# mLRS-tx-dualE22-top-v042.net
KiCad netlist of a schematic drawn in EAGLE
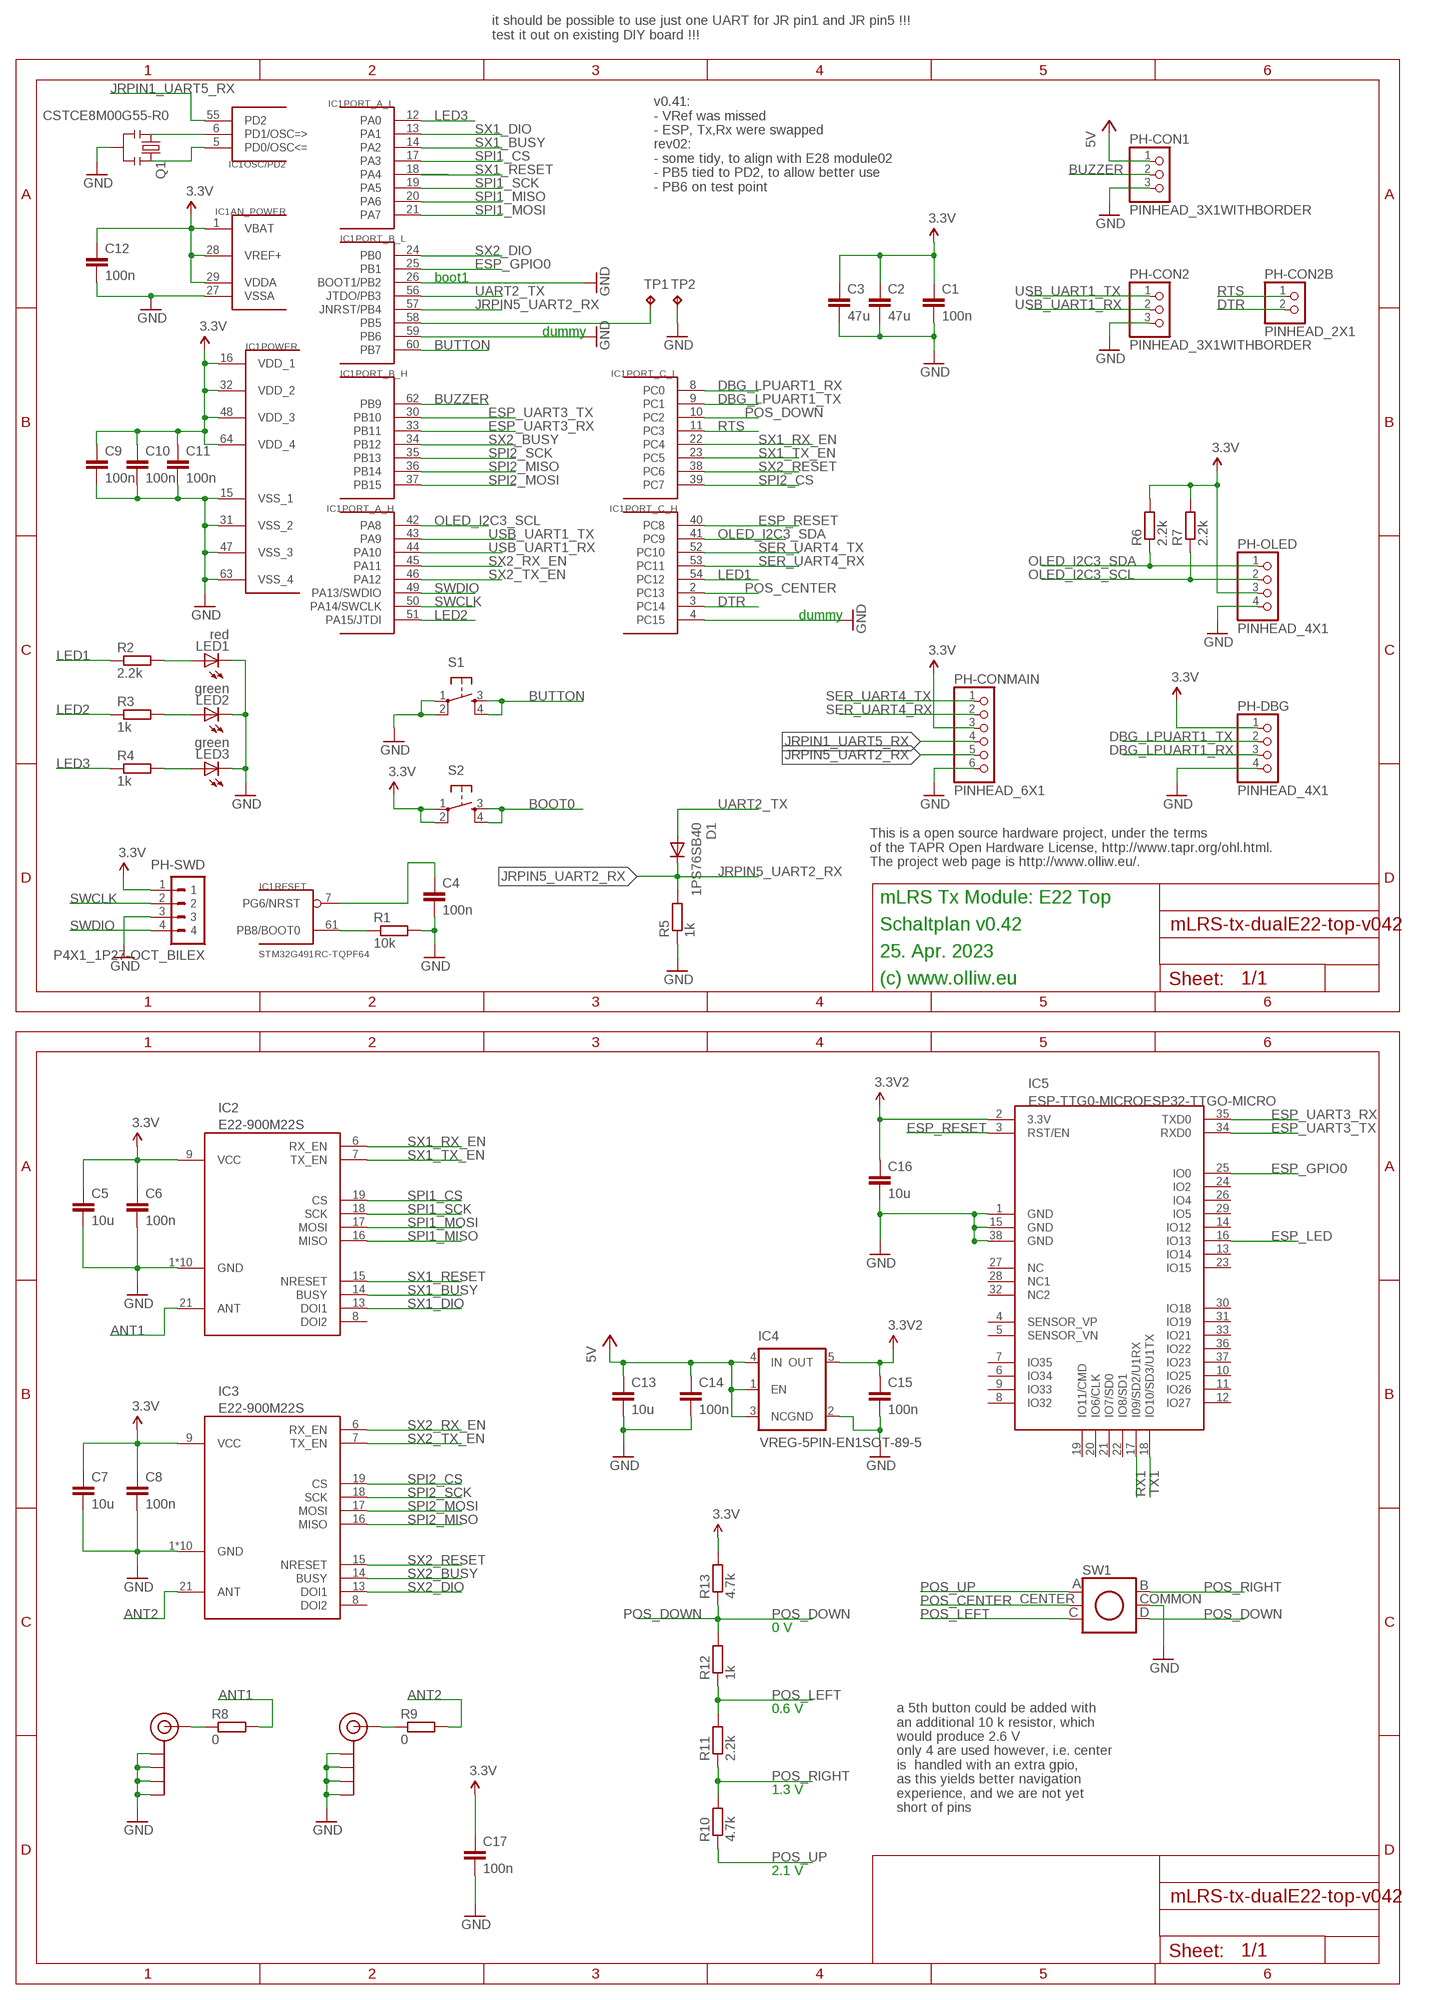
[diagram p0: schematic, sheet 1]

(export (version "E")
  (design (tool "Eeschema 10.0.6"))
  (components
    (comp (ref "C1")
      (value "100n")
      (footprint "eagle-import:C0402")
      (libsource (lib "eagle-import") (part "C-EUC0402"))
    )
    (comp (ref "C2")
      (value "47u")
      (footprint "eagle-import:C1210")
      (libsource (lib "eagle-import") (part "C-EUC1210"))
    )
    (comp (ref "C3")
      (value "47u")
      (footprint "eagle-import:C1206K")
      (libsource (lib "eagle-import") (part "C-EUC1206K"))
    )
    (comp (ref "C4")
      (value "100n")
      (footprint "eagle-import:C0402")
      (libsource (lib "eagle-import") (part "C-EUC0402"))
    )
    (comp (ref "C5")
      (value "10u")
      (footprint "eagle-import:C0603")
      (libsource (lib "eagle-import") (part "C-EUC0603"))
    )
    (comp (ref "C6")
      (value "100n")
      (footprint "eagle-import:C0402")
      (libsource (lib "eagle-import") (part "C-EUC0402"))
    )
    (comp (ref "C7")
      (value "10u")
      (footprint "eagle-import:C0603")
      (libsource (lib "eagle-import") (part "C-EUC0603"))
    )
    (comp (ref "C8")
      (value "100n")
      (footprint "eagle-import:C0402")
      (libsource (lib "eagle-import") (part "C-EUC0402"))
    )
    (comp (ref "C9")
      (value "100n")
      (footprint "eagle-import:C0402")
      (libsource (lib "eagle-import") (part "C-EUC0402"))
    )
    (comp (ref "C10")
      (value "100n")
      (footprint "eagle-import:C0402")
      (libsource (lib "eagle-import") (part "C-EUC0402"))
    )
    (comp (ref "C11")
      (value "100n")
      (footprint "eagle-import:C0402")
      (libsource (lib "eagle-import") (part "C-EUC0402"))
    )
    (comp (ref "C12")
      (value "100n")
      (footprint "eagle-import:C0402")
      (libsource (lib "eagle-import") (part "C-EUC0402"))
    )
    (comp (ref "C13")
      (value "10u")
      (footprint "eagle-import:C0603")
      (libsource (lib "eagle-import") (part "C-EUC0603"))
    )
    (comp (ref "C14")
      (value "100n")
      (footprint "eagle-import:C0402")
      (libsource (lib "eagle-import") (part "C-EUC0402"))
    )
    (comp (ref "C15")
      (value "100n")
      (footprint "eagle-import:C0402")
      (libsource (lib "eagle-import") (part "C-EUC0402"))
    )
    (comp (ref "C16")
      (value "10u")
      (footprint "eagle-import:C0603")
      (libsource (lib "eagle-import") (part "C-EUC0603"))
    )
    (comp (ref "C17")
      (value "100n")
      (footprint "eagle-import:C0402")
      (libsource (lib "eagle-import") (part "C-EUC0402"))
    )
    (comp (ref "D1")
      (value "1PS76SB40")
      (footprint "eagle-import:SOD110-R")
      (libsource (lib "eagle-import") (part "DIODE-SOD110-R"))
    )
    (comp (ref "IC1")
      (value "STM32G491RC-TQPF64")
      (footprint "eagle-import:TQFP64")
      (libsource (lib "eagle-import") (part "STM32G4X1RX-TQPF64"))
    )
    (comp (ref "IC2")
      (value "E22-900M22S")
      (footprint "eagle-import:E22-900M22S")
      (libsource (lib "eagle-import") (part "E22-900M22S"))
    )
    (comp (ref "IC3")
      (value "E22-900M22S")
      (footprint "eagle-import:E22-900M22S")
      (libsource (lib "eagle-import") (part "E22-900M22S"))
    )
    (comp (ref "IC4")
      (value "VREG-5PIN-EN1SOT-89-5")
      (footprint "eagle-import:SOT-89-5")
      (libsource (lib "eagle-import") (part "VREG-5PIN-EN1SOT-89-5"))
    )
    (comp (ref "IC5")
      (value "ESP-TTG0-MICROESP32-TTGO-MICRO")
      (footprint "eagle-import:ESP32-TTGO-MICRO")
      (libsource (lib "eagle-import") (part "ESP-TTG0-MICROESP32-TTGO-MICRO"))
    )
    (comp (ref "LED1")
      (value "red")
      (footprint "eagle-import:CHIPLED_0603")
      (libsource (lib "eagle-import") (part "LEDCHIPLED_0603"))
    )
    (comp (ref "LED2")
      (value "green")
      (footprint "eagle-import:CHIPLED_0603")
      (libsource (lib "eagle-import") (part "LEDCHIPLED_0603"))
    )
    (comp (ref "LED3")
      (value "green")
      (footprint "eagle-import:CHIPLED_0603")
      (libsource (lib "eagle-import") (part "LEDCHIPLED_0603"))
    )
    (comp (ref "PH-CON1")
      (value "PINHEAD_3X1WITHBORDER")
      (footprint "eagle-import:PINHEAD_3X1")
      (libsource (lib "eagle-import") (part "PINHEAD_3X1WITHBORDER"))
    )
    (comp (ref "PH-CON2")
      (value "PINHEAD_3X1WITHBORDER")
      (footprint "eagle-import:PINHEAD_3X1")
      (libsource (lib "eagle-import") (part "PINHEAD_3X1WITHBORDER"))
    )
    (comp (ref "PH-CON2B")
      (value "PINHEAD_2X1")
      (footprint "eagle-import:PINHEAD_2X1")
      (libsource (lib "eagle-import") (part "PINHEAD_2X1"))
    )
    (comp (ref "PH-CONMAIN")
      (value "PINHEAD_6X1")
      (footprint "eagle-import:PINHEAD_6X1")
      (libsource (lib "eagle-import") (part "PINHEAD_6X1"))
    )
    (comp (ref "PH-DBG")
      (value "PINHEAD_4X1")
      (footprint "eagle-import:PINHEAD_4X1")
      (libsource (lib "eagle-import") (part "PINHEAD_4X1"))
    )
    (comp (ref "PH-OLED")
      (value "PINHEAD_4X1")
      (footprint "eagle-import:PINHEAD_4X1")
      (libsource (lib "eagle-import") (part "PINHEAD_4X1"))
    )
    (comp (ref "PH-SWD")
      (value "P4X1_1P27-OCT_BILEX")
      (footprint "eagle-import:4X1_1P27_OCT_BILEX")
      (libsource (lib "eagle-import") (part "P4X1_1P27-OCT_BILEX"))
    )
    (comp (ref "Q1")
      (value "CSTCE8M00G55-R0")
      (footprint "eagle-import:RESONATOR-SMD")
      (libsource (lib "eagle-import") (part "RESONATORSMD"))
    )
    (comp (ref "R1")
      (value "10k")
      (footprint "eagle-import:R0402")
      (libsource (lib "eagle-import") (part "R-EU_R0402"))
    )
    (comp (ref "R2")
      (value "2.2k")
      (footprint "eagle-import:R0402")
      (libsource (lib "eagle-import") (part "R-EU_R0402"))
    )
    (comp (ref "R3")
      (value "1k")
      (footprint "eagle-import:R0402")
      (libsource (lib "eagle-import") (part "R-EU_R0402"))
    )
    (comp (ref "R4")
      (value "1k")
      (footprint "eagle-import:R0402")
      (libsource (lib "eagle-import") (part "R-EU_R0402"))
    )
    (comp (ref "R5")
      (value "1k")
      (footprint "eagle-import:R0402")
      (libsource (lib "eagle-import") (part "R-EU_R0402"))
    )
    (comp (ref "R6")
      (value "2.2k")
      (footprint "eagle-import:R0402")
      (libsource (lib "eagle-import") (part "R-EU_R0402"))
    )
    (comp (ref "R7")
      (value "2.2k")
      (footprint "eagle-import:R0402")
      (libsource (lib "eagle-import") (part "R-EU_R0402"))
    )
    (comp (ref "R8")
      (value "0")
      (footprint "eagle-import:R0402")
      (libsource (lib "eagle-import") (part "R-EU_R0402"))
    )
    (comp (ref "R9")
      (value "0")
      (footprint "eagle-import:R0402")
      (libsource (lib "eagle-import") (part "R-EU_R0402"))
    )
    (comp (ref "R10")
      (value "4.7k")
      (footprint "eagle-import:R0402")
      (libsource (lib "eagle-import") (part "R-EU_R0402"))
    )
    (comp (ref "R11")
      (value "2.2k")
      (footprint "eagle-import:R0402")
      (libsource (lib "eagle-import") (part "R-EU_R0402"))
    )
    (comp (ref "R12")
      (value "1k")
      (footprint "eagle-import:R0402")
      (libsource (lib "eagle-import") (part "R-EU_R0402"))
    )
    (comp (ref "R13")
      (value "4.7k")
      (footprint "eagle-import:R0402")
      (libsource (lib "eagle-import") (part "R-EU_R0402"))
    )
    (comp (ref "RF1")
      (value "SMA_EDGE")
      (footprint "eagle-import:SMA-EDGE")
      (libsource (lib "eagle-import") (part "SMA_EDGE"))
    )
    (comp (ref "RF2")
      (value "SMA_EDGE")
      (footprint "eagle-import:SMA-EDGE")
      (libsource (lib "eagle-import") (part "SMA_EDGE"))
    )
    (comp (ref "S1")
      (value "TAC_SWITCHPTH")
      (footprint "eagle-import:TACTILE-PTH")
      (libsource (lib "eagle-import") (part "TAC_SWITCHPTH"))
    )
    (comp (ref "S2")
      (value "TAC_SWITCHPTH")
      (footprint "eagle-import:TACTILE-PTH")
      (libsource (lib "eagle-import") (part "TAC_SWITCHPTH"))
    )
    (comp (ref "SW1")
      (value "JOYSTICK-5WAY")
      (footprint "eagle-import:JOYSTICK-5WAY")
      (libsource (lib "eagle-import") (part "JOYSTICK-5WAY"))
    )
    (comp (ref "TP1")
      (value "TPB1,27")
      (footprint "eagle-import:B1,27")
      (libsource (lib "eagle-import") (part "TPB1,27"))
    )
    (comp (ref "TP2")
      (value "TPB1,27")
      (footprint "eagle-import:B1,27")
      (libsource (lib "eagle-import") (part "TPB1,27"))
    )
  )
  (nets
    (net (code "1") (name "/ANT1") (class "Default")
      (node (ref "IC2") (pin "21") (pinfunction "ANT_21") (pintype "bidirectional"))
      (node (ref "R8") (pin "2") (pinfunction "2_2") (pintype "passive"))
    )
    (net (code "2") (name "/ANT2") (class "Default")
      (node (ref "IC3") (pin "21") (pinfunction "ANT_21") (pintype "bidirectional"))
      (node (ref "R9") (pin "2") (pinfunction "2_2") (pintype "passive"))
    )
    (net (code "3") (name "/BOOT0") (class "Default")
      (node (ref "IC1") (pin "61") (pinfunction "PB8/BOOT0_61") (pintype "input"))
      (node (ref "R1") (pin "1") (pinfunction "1_1") (pintype "passive"))
      (node (ref "S2") (pin "3") (pinfunction "3_3") (pintype "passive"))
      (node (ref "S2") (pin "4") (pinfunction "4_4") (pintype "passive"))
    )
    (net (code "4") (name "/BUTTON") (class "Default")
      (node (ref "IC1") (pin "60") (pinfunction "PB7_60") (pintype "bidirectional"))
      (node (ref "S1") (pin "3") (pinfunction "3_3") (pintype "passive"))
      (node (ref "S1") (pin "4") (pinfunction "4_4") (pintype "passive"))
    )
    (net (code "5") (name "/BUZZER") (class "Default")
      (node (ref "IC1") (pin "62") (pinfunction "PB9_62") (pintype "bidirectional"))
      (node (ref "PH-CON1") (pin "2") (pinfunction "3_2") (pintype "passive"))
    )
    (net (code "6") (name "/DBG_LPUART1_RX") (class "Default")
      (node (ref "IC1") (pin "8") (pinfunction "PC0_8") (pintype "bidirectional"))
      (node (ref "PH-DBG") (pin "3") (pinfunction "3_3") (pintype "passive"))
    )
    (net (code "7") (name "/DBG_LPUART1_TX") (class "Default")
      (node (ref "IC1") (pin "9") (pinfunction "PC1_9") (pintype "bidirectional"))
      (node (ref "PH-DBG") (pin "2") (pinfunction "2_2") (pintype "passive"))
    )
    (net (code "8") (name "/DTR") (class "Default")
      (node (ref "IC1") (pin "3") (pinfunction "PC14_3") (pintype "bidirectional"))
      (node (ref "PH-CON2B") (pin "2") (pinfunction "2_2") (pintype "passive"))
    )
    (net (code "9") (name "/ESP_GPIO0") (class "Default")
      (node (ref "IC1") (pin "25") (pinfunction "PB1_25") (pintype "bidirectional"))
      (node (ref "IC5") (pin "25") (pinfunction "IO0_25") (pintype "bidirectional"))
    )
    (net (code "10") (name "/ESP_LED") (class "Default")
      (node (ref "IC5") (pin "16") (pinfunction "IO13_16") (pintype "bidirectional"))
    )
    (net (code "11") (name "/ESP_RESET") (class "Default")
      (node (ref "IC1") (pin "40") (pinfunction "PC8_40") (pintype "bidirectional"))
      (node (ref "IC5") (pin "3") (pinfunction "RST/EN_3") (pintype "input"))
    )
    (net (code "12") (name "/ESP_UART3_RX") (class "Default")
      (node (ref "IC1") (pin "33") (pinfunction "PB11_33") (pintype "bidirectional"))
      (node (ref "IC5") (pin "35") (pinfunction "TXD0_35") (pintype "bidirectional"))
    )
    (net (code "13") (name "/ESP_UART3_TX") (class "Default")
      (node (ref "IC1") (pin "30") (pinfunction "PB10_30") (pintype "bidirectional"))
      (node (ref "IC5") (pin "34") (pinfunction "RXD0_34") (pintype "bidirectional"))
    )
    (net (code "14") (name "/LED1") (class "Default")
      (node (ref "IC1") (pin "54") (pinfunction "PC12_54") (pintype "bidirectional"))
      (node (ref "R2") (pin "1") (pinfunction "1_1") (pintype "passive"))
    )
    (net (code "15") (name "/LED2") (class "Default")
      (node (ref "IC1") (pin "51") (pinfunction "PA15/JTDI_51") (pintype "bidirectional"))
      (node (ref "R3") (pin "1") (pinfunction "1_1") (pintype "passive"))
    )
    (net (code "16") (name "/LED3") (class "Default")
      (node (ref "IC1") (pin "12") (pinfunction "PA0_12") (pintype "bidirectional"))
      (node (ref "R4") (pin "1") (pinfunction "1_1") (pintype "passive"))
    )
    (net (code "17") (name "/OLED_I2C3_SCL") (class "Default")
      (node (ref "IC1") (pin "42") (pinfunction "PA8_42") (pintype "bidirectional"))
      (node (ref "PH-OLED") (pin "2") (pinfunction "2_2") (pintype "passive"))
      (node (ref "R7") (pin "1") (pinfunction "1_1") (pintype "passive"))
    )
    (net (code "18") (name "/OLED_I2C3_SDA") (class "Default")
      (node (ref "IC1") (pin "41") (pinfunction "PC9_41") (pintype "bidirectional"))
      (node (ref "PH-OLED") (pin "1") (pinfunction "1_1") (pintype "passive"))
      (node (ref "R6") (pin "1") (pinfunction "1_1") (pintype "passive"))
    )
    (net (code "19") (name "/POS_CENTER") (class "Default")
      (node (ref "IC1") (pin "2") (pinfunction "PC13_2") (pintype "bidirectional"))
      (node (ref "SW1") (pin "2") (pinfunction "CENTER_2") (pintype "bidirectional"))
    )
    (net (code "20") (name "/POS_DOWN") (class "Default")
      (node (ref "IC1") (pin "10") (pinfunction "PC2_10") (pintype "bidirectional"))
      (node (ref "R12") (pin "2") (pinfunction "2_2") (pintype "passive"))
      (node (ref "R13") (pin "1") (pinfunction "1_1") (pintype "passive"))
      (node (ref "SW1") (pin "6") (pinfunction "D_6") (pintype "bidirectional"))
    )
    (net (code "21") (name "/POS_LEFT") (class "Default")
      (node (ref "R11") (pin "2") (pinfunction "2_2") (pintype "passive"))
      (node (ref "R12") (pin "1") (pinfunction "1_1") (pintype "passive"))
      (node (ref "SW1") (pin "3") (pinfunction "C_3") (pintype "bidirectional"))
    )
    (net (code "22") (name "/POS_RIGHT") (class "Default")
      (node (ref "R10") (pin "2") (pinfunction "2_2") (pintype "passive"))
      (node (ref "R11") (pin "1") (pinfunction "1_1") (pintype "passive"))
      (node (ref "SW1") (pin "4") (pinfunction "B_4") (pintype "bidirectional"))
    )
    (net (code "23") (name "/POS_UP") (class "Default")
      (node (ref "R10") (pin "1") (pinfunction "1_1") (pintype "passive"))
      (node (ref "SW1") (pin "1") (pinfunction "A_1") (pintype "bidirectional"))
    )
    (net (code "24") (name "/RTS") (class "Default")
      (node (ref "IC1") (pin "11") (pinfunction "PC3_11") (pintype "bidirectional"))
      (node (ref "PH-CON2B") (pin "1") (pinfunction "1_1") (pintype "passive"))
    )
    (net (code "25") (name "/RX1") (class "Default")
      (node (ref "IC5") (pin "17") (pinfunction "I09/SD2/U1RX_17") (pintype "bidirectional"))
    )
    (net (code "26") (name "/SER_UART4_RX") (class "Default")
      (node (ref "IC1") (pin "53") (pinfunction "PC11_53") (pintype "bidirectional"))
      (node (ref "PH-CONMAIN") (pin "2") (pinfunction "2_2") (pintype "passive"))
    )
    (net (code "27") (name "/SER_UART4_TX") (class "Default")
      (node (ref "IC1") (pin "52") (pinfunction "PC10_52") (pintype "bidirectional"))
      (node (ref "PH-CONMAIN") (pin "1") (pinfunction "1_1") (pintype "passive"))
    )
    (net (code "28") (name "/SPI1_CS") (class "Default")
      (node (ref "IC1") (pin "17") (pinfunction "PA3_17") (pintype "bidirectional"))
      (node (ref "IC2") (pin "19") (pinfunction "CS_19") (pintype "bidirectional"))
    )
    (net (code "29") (name "/SPI1_MISO") (class "Default")
      (node (ref "IC1") (pin "20") (pinfunction "PA6_20") (pintype "bidirectional"))
      (node (ref "IC2") (pin "16") (pinfunction "MISO_16") (pintype "bidirectional"))
    )
    (net (code "30") (name "/SPI1_MOSI") (class "Default")
      (node (ref "IC1") (pin "21") (pinfunction "PA7_21") (pintype "bidirectional"))
      (node (ref "IC2") (pin "17") (pinfunction "MOSI_17") (pintype "bidirectional"))
    )
    (net (code "31") (name "/SPI1_SCK") (class "Default")
      (node (ref "IC1") (pin "19") (pinfunction "PA5_19") (pintype "bidirectional"))
      (node (ref "IC2") (pin "18") (pinfunction "SCK_18") (pintype "bidirectional"))
    )
    (net (code "32") (name "/SPI2_CS") (class "Default")
      (node (ref "IC1") (pin "39") (pinfunction "PC7_39") (pintype "bidirectional"))
      (node (ref "IC3") (pin "19") (pinfunction "CS_19") (pintype "bidirectional"))
    )
    (net (code "33") (name "/SPI2_MISO") (class "Default")
      (node (ref "IC1") (pin "36") (pinfunction "PB14_36") (pintype "bidirectional"))
      (node (ref "IC3") (pin "16") (pinfunction "MISO_16") (pintype "bidirectional"))
    )
    (net (code "34") (name "/SPI2_MOSI") (class "Default")
      (node (ref "IC1") (pin "37") (pinfunction "PB15_37") (pintype "bidirectional"))
      (node (ref "IC3") (pin "17") (pinfunction "MOSI_17") (pintype "bidirectional"))
    )
    (net (code "35") (name "/SPI2_SCK") (class "Default")
      (node (ref "IC1") (pin "35") (pinfunction "PB13_35") (pintype "bidirectional"))
      (node (ref "IC3") (pin "18") (pinfunction "SCK_18") (pintype "bidirectional"))
    )
    (net (code "36") (name "/SWCLK") (class "Default")
      (node (ref "IC1") (pin "50") (pinfunction "PA14/SWCLK_50") (pintype "bidirectional"))
      (node (ref "PH-SWD") (pin "2") (pinfunction "2_2") (pintype "passive"))
    )
    (net (code "37") (name "/SWDIO") (class "Default")
      (node (ref "IC1") (pin "49") (pinfunction "PA13/SWDIO_49") (pintype "bidirectional"))
      (node (ref "PH-SWD") (pin "4") (pinfunction "4_4") (pintype "passive"))
    )
    (net (code "38") (name "/SX1_BUSY") (class "Default")
      (node (ref "IC1") (pin "14") (pinfunction "PA2_14") (pintype "bidirectional"))
      (node (ref "IC2") (pin "14") (pinfunction "BUSY_14") (pintype "bidirectional"))
    )
    (net (code "39") (name "/SX1_DIO") (class "Default")
      (node (ref "IC1") (pin "13") (pinfunction "PA1_13") (pintype "bidirectional"))
      (node (ref "IC2") (pin "13") (pinfunction "DOI1_13") (pintype "bidirectional"))
    )
    (net (code "40") (name "/SX1_RESET") (class "Default")
      (node (ref "IC1") (pin "18") (pinfunction "PA4_18") (pintype "bidirectional"))
      (node (ref "IC2") (pin "15") (pinfunction "NRESET_15") (pintype "input"))
    )
    (net (code "41") (name "/SX1_RX_EN") (class "Default")
      (node (ref "IC1") (pin "22") (pinfunction "PC4_22") (pintype "bidirectional"))
      (node (ref "IC2") (pin "6") (pinfunction "RX_EN_6") (pintype "bidirectional"))
    )
    (net (code "42") (name "/SX1_TX_EN") (class "Default")
      (node (ref "IC1") (pin "23") (pinfunction "PC5_23") (pintype "bidirectional"))
      (node (ref "IC2") (pin "7") (pinfunction "TX_EN_7") (pintype "bidirectional"))
    )
    (net (code "43") (name "/SX2_BUSY") (class "Default")
      (node (ref "IC1") (pin "34") (pinfunction "PB12_34") (pintype "bidirectional"))
      (node (ref "IC3") (pin "14") (pinfunction "BUSY_14") (pintype "bidirectional"))
    )
    (net (code "44") (name "/SX2_DIO") (class "Default")
      (node (ref "IC1") (pin "24") (pinfunction "PB0_24") (pintype "bidirectional"))
      (node (ref "IC3") (pin "13") (pinfunction "DOI1_13") (pintype "bidirectional"))
    )
    (net (code "45") (name "/SX2_RESET") (class "Default")
      (node (ref "IC1") (pin "38") (pinfunction "PC6_38") (pintype "bidirectional"))
      (node (ref "IC3") (pin "15") (pinfunction "NRESET_15") (pintype "input"))
    )
    (net (code "46") (name "/SX2_RX_EN") (class "Default")
      (node (ref "IC1") (pin "45") (pinfunction "PA11_45") (pintype "bidirectional"))
      (node (ref "IC3") (pin "6") (pinfunction "RX_EN_6") (pintype "bidirectional"))
    )
    (net (code "47") (name "/SX2_TX_EN") (class "Default")
      (node (ref "IC1") (pin "46") (pinfunction "PA12_46") (pintype "bidirectional"))
      (node (ref "IC3") (pin "7") (pinfunction "TX_EN_7") (pintype "bidirectional"))
    )
    (net (code "48") (name "/TX1") (class "Default")
      (node (ref "IC5") (pin "18") (pinfunction "IO10/SD3/U1TX_18") (pintype "bidirectional"))
    )
    (net (code "49") (name "/UART2_TX") (class "Default")
      (node (ref "D1") (pin "A") (pinfunction "A_A") (pintype "passive"))
      (node (ref "IC1") (pin "56") (pinfunction "JTDO/PB3_56") (pintype "bidirectional"))
    )
    (net (code "50") (name "/USB_UART1_RX") (class "Default")
      (node (ref "IC1") (pin "44") (pinfunction "PA10_44") (pintype "bidirectional"))
      (node (ref "PH-CON2") (pin "2") (pinfunction "3_2") (pintype "passive"))
    )
    (net (code "51") (name "/USB_UART1_TX") (class "Default")
      (node (ref "IC1") (pin "43") (pinfunction "PA9_43") (pintype "bidirectional"))
      (node (ref "PH-CON2") (pin "1") (pinfunction "1_1") (pintype "passive"))
    )
    (net (code "52") (name "3.3V") (class "Default")
      (node (ref "C1") (pin "1") (pinfunction "1_1") (pintype "passive"))
      (node (ref "C10") (pin "1") (pinfunction "1_1") (pintype "passive"))
      (node (ref "C11") (pin "1") (pinfunction "1_1") (pintype "passive"))
      (node (ref "C12") (pin "1") (pinfunction "1_1") (pintype "passive"))
      (node (ref "C17") (pin "1") (pinfunction "1_1") (pintype "passive"))
      (node (ref "C2") (pin "1") (pinfunction "1_1") (pintype "passive"))
      (node (ref "C3") (pin "1") (pinfunction "1_1") (pintype "passive"))
      (node (ref "C5") (pin "1") (pinfunction "1_1") (pintype "passive"))
      (node (ref "C6") (pin "1") (pinfunction "1_1") (pintype "passive"))
      (node (ref "C7") (pin "1") (pinfunction "1_1") (pintype "passive"))
      (node (ref "C8") (pin "1") (pinfunction "1_1") (pintype "passive"))
      (node (ref "C9") (pin "1") (pinfunction "1_1") (pintype "passive"))
      (node (ref "IC1") (pin "1") (pinfunction "VBAT_1") (pintype "power_in"))
      (node (ref "IC1") (pin "16") (pinfunction "VDD_1_16") (pintype "power_in"))
      (node (ref "IC1") (pin "28") (pinfunction "VREF+_28") (pintype "input"))
      (node (ref "IC1") (pin "29") (pinfunction "VDDA_29") (pintype "power_in"))
      (node (ref "IC1") (pin "32") (pinfunction "VDD_2_32") (pintype "power_in"))
      (node (ref "IC1") (pin "48") (pinfunction "VDD_3_48") (pintype "power_in"))
      (node (ref "IC1") (pin "64") (pinfunction "VDD_4_64") (pintype "power_in"))
      (node (ref "IC2") (pin "9") (pinfunction "VCC_9") (pintype "power_in"))
      (node (ref "IC3") (pin "9") (pinfunction "VCC_9") (pintype "power_in"))
      (node (ref "PH-CONMAIN") (pin "3") (pinfunction "3_3") (pintype "passive"))
      (node (ref "PH-DBG") (pin "1") (pinfunction "1_1") (pintype "passive"))
      (node (ref "PH-OLED") (pin "3") (pinfunction "3_3") (pintype "passive"))
      (node (ref "PH-SWD") (pin "1") (pinfunction "1_1") (pintype "passive"))
      (node (ref "R13") (pin "2") (pinfunction "2_2") (pintype "passive"))
      (node (ref "R6") (pin "2") (pinfunction "2_2") (pintype "passive"))
      (node (ref "R7") (pin "2") (pinfunction "2_2") (pintype "passive"))
      (node (ref "S2") (pin "1") (pinfunction "1_1") (pintype "passive"))
      (node (ref "S2") (pin "2") (pinfunction "2_2") (pintype "passive"))
    )
    (net (code "53") (name "3.3V2") (class "Default")
      (node (ref "C15") (pin "1") (pinfunction "1_1") (pintype "passive"))
      (node (ref "C16") (pin "1") (pinfunction "1_1") (pintype "passive"))
      (node (ref "IC4") (pin "5") (pinfunction "OUT_5") (pintype "output"))
      (node (ref "IC5") (pin "2") (pinfunction "3.3V_2") (pintype "power_in"))
    )
    (net (code "54") (name "5V") (class "Default")
      (node (ref "C13") (pin "1") (pinfunction "1_1") (pintype "passive"))
      (node (ref "C14") (pin "1") (pinfunction "1_1") (pintype "passive"))
      (node (ref "IC4") (pin "1") (pinfunction "EN_1") (pintype "input"))
      (node (ref "IC4") (pin "3") (pinfunction "NC_3") (pintype "passive"))
      (node (ref "IC4") (pin "4") (pinfunction "IN_4") (pintype "power_in"))
      (node (ref "PH-CON1") (pin "1") (pinfunction "1_1") (pintype "passive"))
    )
    (net (code "55") (name "GND") (class "Default")
      (node (ref "C1") (pin "2") (pinfunction "2_2") (pintype "passive"))
      (node (ref "C10") (pin "2") (pinfunction "2_2") (pintype "passive"))
      (node (ref "C11") (pin "2") (pinfunction "2_2") (pintype "passive"))
      (node (ref "C12") (pin "2") (pinfunction "2_2") (pintype "passive"))
      (node (ref "C13") (pin "2") (pinfunction "2_2") (pintype "passive"))
      (node (ref "C14") (pin "2") (pinfunction "2_2") (pintype "passive"))
      (node (ref "C15") (pin "2") (pinfunction "2_2") (pintype "passive"))
      (node (ref "C16") (pin "2") (pinfunction "2_2") (pintype "passive"))
      (node (ref "C17") (pin "2") (pinfunction "2_2") (pintype "passive"))
      (node (ref "C2") (pin "2") (pinfunction "2_2") (pintype "passive"))
      (node (ref "C3") (pin "2") (pinfunction "2_2") (pintype "passive"))
      (node (ref "C4") (pin "2") (pinfunction "2_2") (pintype "passive"))
      (node (ref "C5") (pin "2") (pinfunction "2_2") (pintype "passive"))
      (node (ref "C6") (pin "2") (pinfunction "2_2") (pintype "passive"))
      (node (ref "C7") (pin "2") (pinfunction "2_2") (pintype "passive"))
      (node (ref "C8") (pin "2") (pinfunction "2_2") (pintype "passive"))
      (node (ref "C9") (pin "2") (pinfunction "2_2") (pintype "passive"))
      (node (ref "IC1") (pin "15") (pinfunction "VSS_1_15") (pintype "power_in"))
      (node (ref "IC1") (pin "26") (pinfunction "BOOT1/PB2_26") (pintype "bidirectional"))
      (node (ref "IC1") (pin "27") (pinfunction "VSSA_27") (pintype "power_in"))
      (node (ref "IC1") (pin "31") (pinfunction "VSS_2_31") (pintype "power_in"))
      (node (ref "IC1") (pin "4") (pinfunction "PC15_4") (pintype "bidirectional"))
      (node (ref "IC1") (pin "47") (pinfunction "VSS_3_47") (pintype "power_in"))
      (node (ref "IC1") (pin "59") (pinfunction "PB6_59") (pintype "bidirectional"))
      (node (ref "IC1") (pin "63") (pinfunction "VSS_4_63") (pintype "power_in"))
      (node (ref "IC2") (pin "1") (pinfunction "GND_1") (pintype "power_in"))
      (node (ref "IC2") (pin "10") (pinfunction "GND_10") (pintype "power_in"))
      (node (ref "IC2") (pin "11") (pinfunction "GND_11") (pintype "power_in"))
      (node (ref "IC2") (pin "12") (pinfunction "GND_12") (pintype "power_in"))
      (node (ref "IC2") (pin "2") (pinfunction "GND_2") (pintype "power_in"))
      (node (ref "IC2") (pin "20") (pinfunction "GND_20") (pintype "power_in"))
      (node (ref "IC2") (pin "22") (pinfunction "GND_22") (pintype "power_in"))
      (node (ref "IC2") (pin "3") (pinfunction "GND_3") (pintype "power_in"))
      (node (ref "IC2") (pin "4") (pinfunction "GND_4") (pintype "power_in"))
      (node (ref "IC2") (pin "5") (pinfunction "GND_5") (pintype "power_in"))
      (node (ref "IC3") (pin "1") (pinfunction "GND_1") (pintype "power_in"))
      (node (ref "IC3") (pin "10") (pinfunction "GND_10") (pintype "power_in"))
      (node (ref "IC3") (pin "11") (pinfunction "GND_11") (pintype "power_in"))
      (node (ref "IC3") (pin "12") (pinfunction "GND_12") (pintype "power_in"))
      (node (ref "IC3") (pin "2") (pinfunction "GND_2") (pintype "power_in"))
      (node (ref "IC3") (pin "20") (pinfunction "GND_20") (pintype "power_in"))
      (node (ref "IC3") (pin "22") (pinfunction "GND_22") (pintype "power_in"))
      (node (ref "IC3") (pin "3") (pinfunction "GND_3") (pintype "power_in"))
      (node (ref "IC3") (pin "4") (pinfunction "GND_4") (pintype "power_in"))
      (node (ref "IC3") (pin "5") (pinfunction "GND_5") (pintype "power_in"))
      (node (ref "IC4") (pin "2") (pinfunction "GND_2") (pintype "power_in"))
      (node (ref "IC5") (pin "1") (pinfunction "GND_1") (pintype "power_in"))
      (node (ref "IC5") (pin "15") (pinfunction "GND_15") (pintype "power_in"))
      (node (ref "IC5") (pin "38") (pinfunction "GND_38") (pintype "power_in"))
      (node (ref "LED1") (pin "C") (pinfunction "C_C") (pintype "passive"))
      (node (ref "LED2") (pin "C") (pinfunction "C_C") (pintype "passive"))
      (node (ref "LED3") (pin "C") (pinfunction "C_C") (pintype "passive"))
      (node (ref "PH-CON1") (pin "3") (pinfunction "5_3") (pintype "passive"))
      (node (ref "PH-CON2") (pin "3") (pinfunction "5_3") (pintype "passive"))
      (node (ref "PH-CONMAIN") (pin "6") (pinfunction "6_6") (pintype "passive"))
      (node (ref "PH-DBG") (pin "4") (pinfunction "4_4") (pintype "passive"))
      (node (ref "PH-OLED") (pin "4") (pinfunction "4_4") (pintype "passive"))
      (node (ref "PH-SWD") (pin "3") (pinfunction "3_3") (pintype "passive"))
      (node (ref "Q1") (pin "2") (pinfunction "2_2") (pintype "passive"))
      (node (ref "R1") (pin "2") (pinfunction "2_2") (pintype "passive"))
      (node (ref "R5") (pin "1") (pinfunction "1_1") (pintype "passive"))
      (node (ref "RF1") (pin "GND@0") (pinfunction "GND_GND@0") (pintype "bidirectional"))
      (node (ref "RF1") (pin "GND@1") (pinfunction "GND_GND@1") (pintype "bidirectional"))
      (node (ref "RF1") (pin "GND@2") (pinfunction "GND_GND@2") (pintype "bidirectional"))
      (node (ref "RF1") (pin "GND@3") (pinfunction "GND_GND@3") (pintype "bidirectional"))
      (node (ref "RF2") (pin "GND@0") (pinfunction "GND_GND@0") (pintype "bidirectional"))
      (node (ref "RF2") (pin "GND@1") (pinfunction "GND_GND@1") (pintype "bidirectional"))
      (node (ref "RF2") (pin "GND@2") (pinfunction "GND_GND@2") (pintype "bidirectional"))
      (node (ref "RF2") (pin "GND@3") (pinfunction "GND_GND@3") (pintype "bidirectional"))
      (node (ref "S1") (pin "1") (pinfunction "1_1") (pintype "passive"))
      (node (ref "S1") (pin "2") (pinfunction "2_2") (pintype "passive"))
      (node (ref "SW1") (pin "5") (pinfunction "COMMON_5") (pintype "bidirectional"))
      (node (ref "TP2") (pin "TP") (pinfunction "TP_TP") (pintype "input"))
    )
    (net (code "56") (name "JRPIN1_UART5_RX") (class "Default")
      (node (ref "IC1") (pin "55") (pinfunction "PD2_55") (pintype "bidirectional"))
      (node (ref "PH-CONMAIN") (pin "4") (pinfunction "4_4") (pintype "passive"))
    )
    (net (code "57") (name "JRPIN5_UART2_RX") (class "Default")
      (node (ref "D1") (pin "C") (pinfunction "C_C") (pintype "passive"))
      (node (ref "IC1") (pin "57") (pinfunction "JNRST/PB4_57") (pintype "bidirectional"))
      (node (ref "PH-CONMAIN") (pin "5") (pinfunction "5_5") (pintype "passive"))
      (node (ref "R5") (pin "2") (pinfunction "2_2") (pintype "passive"))
    )
    (net (code "58") (name "Net-(IC1B-PD0{slash}OSC<=)") (class "Default")
      (node (ref "IC1") (pin "5") (pinfunction "PD0/OSC<=_5") (pintype "bidirectional"))
      (node (ref "Q1") (pin "3") (pinfunction "3_3") (pintype "passive"))
    )
    (net (code "59") (name "Net-(IC1B-PD1{slash}OSC=>)") (class "Default")
      (node (ref "IC1") (pin "6") (pinfunction "PD1/OSC=>_6") (pintype "bidirectional"))
      (node (ref "Q1") (pin "1") (pinfunction "1_1") (pintype "passive"))
    )
    (net (code "60") (name "Net-(IC1F-PB5)") (class "Default")
      (node (ref "IC1") (pin "58") (pinfunction "PB5_58") (pintype "bidirectional"))
      (node (ref "TP1") (pin "TP") (pinfunction "TP_TP") (pintype "input"))
    )
    (net (code "61") (name "Net-(IC1J-PG6{slash}NRST)") (class "Default")
      (node (ref "C4") (pin "1") (pinfunction "1_1") (pintype "passive"))
      (node (ref "IC1") (pin "7") (pinfunction "PG6/NRST_7") (pintype "input"))
    )
    (net (code "62") (name "Net-(LED1-PadA)") (class "Default")
      (node (ref "LED1") (pin "A") (pinfunction "A_A") (pintype "passive"))
      (node (ref "R2") (pin "2") (pinfunction "2_2") (pintype "passive"))
    )
    (net (code "63") (name "Net-(LED2-PadA)") (class "Default")
      (node (ref "LED2") (pin "A") (pinfunction "A_A") (pintype "passive"))
      (node (ref "R3") (pin "2") (pinfunction "2_2") (pintype "passive"))
    )
    (net (code "64") (name "Net-(LED3-PadA)") (class "Default")
      (node (ref "LED3") (pin "A") (pinfunction "A_A") (pintype "passive"))
      (node (ref "R4") (pin "2") (pinfunction "2_2") (pintype "passive"))
    )
    (net (code "65") (name "Net-(RF1-SIGNAL)") (class "Default")
      (node (ref "R8") (pin "1") (pinfunction "1_1") (pintype "passive"))
      (node (ref "RF1") (pin "SIG") (pinfunction "SIGNAL_SIG") (pintype "bidirectional"))
    )
    (net (code "66") (name "Net-(RF2-SIGNAL)") (class "Default")
      (node (ref "R9") (pin "1") (pinfunction "1_1") (pintype "passive"))
      (node (ref "RF2") (pin "SIG") (pinfunction "SIGNAL_SIG") (pintype "bidirectional"))
    )
    (net (code "67") (name "unconnected-(IC2-DOI2-Pad8)") (class "Default")
      (node (ref "IC2") (pin "8") (pinfunction "DOI2_8") (pintype "bidirectional"))
    )
    (net (code "68") (name "unconnected-(IC3-DOI2-Pad8)") (class "Default")
      (node (ref "IC3") (pin "8") (pinfunction "DOI2_8") (pintype "bidirectional"))
    )
    (net (code "69") (name "unconnected-(IC5-IO2-Pad24)") (class "Default")
      (node (ref "IC5") (pin "24") (pinfunction "IO2_24") (pintype "bidirectional"))
    )
    (net (code "70") (name "unconnected-(IC5-IO4-Pad26)") (class "Default")
      (node (ref "IC5") (pin "26") (pinfunction "IO4_26") (pintype "bidirectional"))
    )
    (net (code "71") (name "unconnected-(IC5-IO5-Pad29)") (class "Default")
      (node (ref "IC5") (pin "29") (pinfunction "IO5_29") (pintype "bidirectional"))
    )
    (net (code "72") (name "unconnected-(IC5-IO6{slash}CLK-Pad20)") (class "Default")
      (node (ref "IC5") (pin "20") (pinfunction "IO6/CLK_20") (pintype "bidirectional"))
    )
    (net (code "73") (name "unconnected-(IC5-IO7{slash}SD0-Pad21)") (class "Default")
      (node (ref "IC5") (pin "21") (pinfunction "IO7/SD0_21") (pintype "bidirectional"))
    )
    (net (code "74") (name "unconnected-(IC5-IO8{slash}SD1-Pad22)") (class "Default")
      (node (ref "IC5") (pin "22") (pinfunction "IO8/SD1_22") (pintype "bidirectional"))
    )
    (net (code "75") (name "unconnected-(IC5-IO11{slash}CMD-Pad19)") (class "Default")
      (node (ref "IC5") (pin "19") (pinfunction "IO11/CMD_19") (pintype "bidirectional"))
    )
    (net (code "76") (name "unconnected-(IC5-IO12-Pad14)") (class "Default")
      (node (ref "IC5") (pin "14") (pinfunction "IO12_14") (pintype "bidirectional"))
    )
    (net (code "77") (name "unconnected-(IC5-IO14-Pad13)") (class "Default")
      (node (ref "IC5") (pin "13") (pinfunction "IO14_13") (pintype "bidirectional"))
    )
    (net (code "78") (name "unconnected-(IC5-IO15-Pad23)") (class "Default")
      (node (ref "IC5") (pin "23") (pinfunction "IO15_23") (pintype "bidirectional"))
    )
    (net (code "79") (name "unconnected-(IC5-IO18-Pad30)") (class "Default")
      (node (ref "IC5") (pin "30") (pinfunction "IO18_30") (pintype "bidirectional"))
    )
    (net (code "80") (name "unconnected-(IC5-IO19-Pad31)") (class "Default")
      (node (ref "IC5") (pin "31") (pinfunction "IO19_31") (pintype "bidirectional"))
    )
    (net (code "81") (name "unconnected-(IC5-IO21-Pad33)") (class "Default")
      (node (ref "IC5") (pin "33") (pinfunction "IO21_33") (pintype "bidirectional"))
    )
    (net (code "82") (name "unconnected-(IC5-IO22-Pad36)") (class "Default")
      (node (ref "IC5") (pin "36") (pinfunction "IO22_36") (pintype "bidirectional"))
    )
    (net (code "83") (name "unconnected-(IC5-IO23-Pad37)") (class "Default")
      (node (ref "IC5") (pin "37") (pinfunction "IO23_37") (pintype "bidirectional"))
    )
    (net (code "84") (name "unconnected-(IC5-IO25-Pad10)") (class "Default")
      (node (ref "IC5") (pin "10") (pinfunction "IO25_10") (pintype "bidirectional"))
    )
    (net (code "85") (name "unconnected-(IC5-IO26-Pad11)") (class "Default")
      (node (ref "IC5") (pin "11") (pinfunction "IO26_11") (pintype "bidirectional"))
    )
    (net (code "86") (name "unconnected-(IC5-IO27-Pad12)") (class "Default")
      (node (ref "IC5") (pin "12") (pinfunction "IO27_12") (pintype "bidirectional"))
    )
    (net (code "87") (name "unconnected-(IC5-IO32-Pad8)") (class "Default")
      (node (ref "IC5") (pin "8") (pinfunction "IO32_8") (pintype "bidirectional"))
    )
    (net (code "88") (name "unconnected-(IC5-IO33-Pad9)") (class "Default")
      (node (ref "IC5") (pin "9") (pinfunction "IO33_9") (pintype "bidirectional"))
    )
    (net (code "89") (name "unconnected-(IC5-IO34-Pad6)") (class "Default")
      (node (ref "IC5") (pin "6") (pinfunction "IO34_6") (pintype "bidirectional"))
    )
    (net (code "90") (name "unconnected-(IC5-IO35-Pad7)") (class "Default")
      (node (ref "IC5") (pin "7") (pinfunction "IO35_7") (pintype "bidirectional"))
    )
    (net (code "91") (name "unconnected-(IC5-NC-Pad27)") (class "Default")
      (node (ref "IC5") (pin "27") (pinfunction "NC_27") (pintype "no_connect"))
    )
    (net (code "92") (name "unconnected-(IC5-NC1-Pad28)") (class "Default")
      (node (ref "IC5") (pin "28") (pinfunction "NC1_28") (pintype "no_connect"))
    )
    (net (code "93") (name "unconnected-(IC5-NC2-Pad32)") (class "Default")
      (node (ref "IC5") (pin "32") (pinfunction "NC2_32") (pintype "no_connect"))
    )
    (net (code "94") (name "unconnected-(IC5-SENSOR_VN-Pad5)") (class "Default")
      (node (ref "IC5") (pin "5") (pinfunction "SENSOR_VN_5") (pintype "bidirectional"))
    )
    (net (code "95") (name "unconnected-(IC5-SENSOR_VP-Pad4)") (class "Default")
      (node (ref "IC5") (pin "4") (pinfunction "SENSOR_VP_4") (pintype "bidirectional"))
    )
  )
)
